# V1_EG7.net
KiCad netlist of a schematic drawn in EAGLE
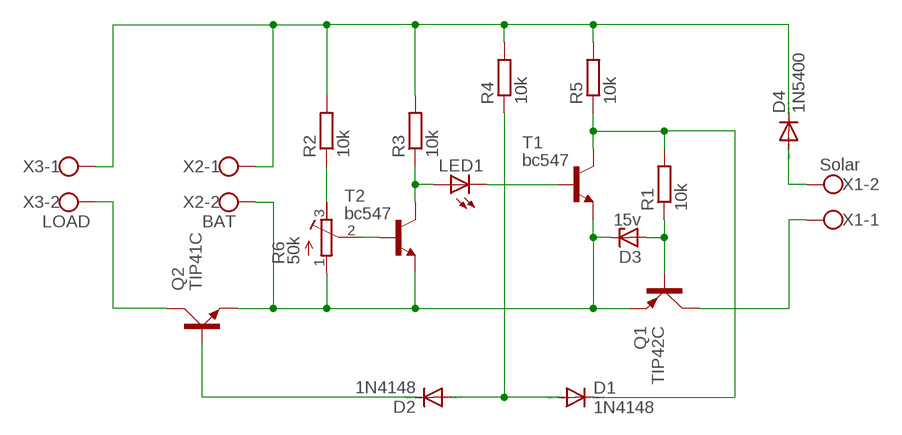
[diagram p0: schematic, sheet 1]

(export (version "E")
  (design (tool "Eeschema 10.0.6"))
  (components
    (comp (ref "D1")
      (value "1N4148")
      (footprint "eagle-import:DO35-10")
      (libsource (lib "eagle-import") (part "1N4148DO35-10"))
    )
    (comp (ref "D2")
      (value "1N4148")
      (footprint "eagle-import:DO35-10")
      (libsource (lib "eagle-import") (part "1N4148DO35-10"))
    )
    (comp (ref "D3")
      (value "15v")
      (footprint "eagle-import:ZDIO-10")
      (libsource (lib "eagle-import") (part "ZENER-DIODEZD-10"))
    )
    (comp (ref "D4")
      (value "1N5400")
      (footprint "eagle-import:DO201-15")
      (libsource (lib "eagle-import") (part "1N5400"))
    )
    (comp (ref "LED1")
      (value "LED5MM")
      (footprint "eagle-import:LED5MM")
      (libsource (lib "eagle-import") (part "LED5MM"))
    )
    (comp (ref "Q1")
      (value "TIP42C")
      (footprint "eagle-import:TO220AV")
      (libsource (lib "eagle-import") (part "TIP42C"))
    )
    (comp (ref "Q2")
      (value "TIP41C")
      (footprint "eagle-import:TO220AV")
      (libsource (lib "eagle-import") (part "TIP41C"))
    )
    (comp (ref "R1")
      (value "10k")
      (footprint "eagle-import:0207_10")
      (libsource (lib "eagle-import") (part "R-EU_0207/10"))
    )
    (comp (ref "R2")
      (value "10k")
      (footprint "eagle-import:0207_10")
      (libsource (lib "eagle-import") (part "R-EU_0207/10"))
    )
    (comp (ref "R3")
      (value "10k")
      (footprint "eagle-import:0207_10")
      (libsource (lib "eagle-import") (part "R-EU_0207/10"))
    )
    (comp (ref "R4")
      (value "10k")
      (footprint "eagle-import:0207_10")
      (libsource (lib "eagle-import") (part "R-EU_0207/10"))
    )
    (comp (ref "R5")
      (value "10k")
      (footprint "eagle-import:0207_10")
      (libsource (lib "eagle-import") (part "R-EU_0207/10"))
    )
    (comp (ref "R6")
      (value "50k")
      (footprint "eagle-import:RTRIM64W")
      (libsource (lib "eagle-import") (part "R-TRIMM64W"))
    )
    (comp (ref "T1")
      (value "bc547")
      (footprint "eagle-import:TO92-CBE")
      (libsource (lib "eagle-import") (part "-NPN-TO92-CBEBC547"))
    )
    (comp (ref "T2")
      (value "bc547")
      (footprint "eagle-import:TO92-CBE")
      (libsource (lib "eagle-import") (part "-NPN-TO92-CBEBC547"))
    )
    (comp (ref "X1")
      (value "Solar")
      (footprint "eagle-import:W237-102")
      (fields (field (name "MPN") "237-102"))
      (libsource (lib "eagle-import") (part "W237-102"))
    )
    (comp (ref "X2")
      (value "BAT")
      (footprint "eagle-import:W237-102")
      (fields (field (name "MPN") "237-102"))
      (libsource (lib "eagle-import") (part "W237-102"))
    )
    (comp (ref "X3")
      (value "LOAD")
      (footprint "eagle-import:W237-102")
      (fields (field (name "MPN") "237-102"))
      (libsource (lib "eagle-import") (part "W237-102"))
    )
  )
  (nets
    (net (code "1") (name "Net-(D1-PadA)") (class "Default")
      (node (ref "D1") (pin "A") (pinfunction "A_A") (pintype "passive"))
      (node (ref "D2") (pin "A") (pinfunction "A_A") (pintype "passive"))
      (node (ref "R4") (pin "1") (pinfunction "1_1") (pintype "passive"))
    )
    (net (code "2") (name "Net-(D1-PadC)") (class "Default")
      (node (ref "D1") (pin "C") (pinfunction "C_C") (pintype "passive"))
      (node (ref "R1") (pin "2") (pinfunction "2_2") (pintype "passive"))
      (node (ref "R5") (pin "1") (pinfunction "1_1") (pintype "passive"))
      (node (ref "T1") (pin "C") (pinfunction "C_C") (pintype "passive"))
    )
    (net (code "3") (name "Net-(D2-PadC)") (class "Default")
      (node (ref "D2") (pin "C") (pinfunction "C_C") (pintype "passive"))
      (node (ref "Q2") (pin "B") (pinfunction "B_B") (pintype "passive"))
    )
    (net (code "4") (name "Net-(D3-PadA)") (class "Default")
      (node (ref "D3") (pin "A") (pinfunction "A_A") (pintype "passive"))
      (node (ref "Q1") (pin "B") (pinfunction "B_B") (pintype "passive"))
      (node (ref "R1") (pin "1") (pinfunction "1_1") (pintype "passive"))
    )
    (net (code "5") (name "Net-(LED1-C)") (class "Default")
      (node (ref "LED1") (pin "K") (pinfunction "C_K") (pintype "passive"))
      (node (ref "T1") (pin "B") (pinfunction "B_B") (pintype "passive"))
    )
    (net (code "6") (name "Net-(LED1-PadA)") (class "Default")
      (node (ref "LED1") (pin "A") (pinfunction "A_A") (pintype "passive"))
      (node (ref "R3") (pin "1") (pinfunction "1_1") (pintype "passive"))
      (node (ref "T2") (pin "C") (pinfunction "C_C") (pintype "passive"))
    )
    (net (code "7") (name "Net-(R6-A)") (class "Default")
      (node (ref "D3") (pin "C") (pinfunction "C_C") (pintype "passive"))
      (node (ref "Q1") (pin "E") (pinfunction "E_E") (pintype "passive"))
      (node (ref "Q2") (pin "E") (pinfunction "E_E") (pintype "passive"))
      (node (ref "R6") (pin "1") (pinfunction "A_1") (pintype "passive"))
      (node (ref "T1") (pin "E") (pinfunction "E_E") (pintype "passive"))
      (node (ref "T2") (pin "E") (pinfunction "E_E") (pintype "passive"))
      (node (ref "X2") (pin "2") (pinfunction "KL_2") (pintype "passive"))
    )
    (net (code "8") (name "Net-(R6-E)") (class "Default")
      (node (ref "R2") (pin "1") (pinfunction "1_1") (pintype "passive"))
      (node (ref "R6") (pin "3") (pinfunction "E_3") (pintype "passive"))
    )
    (net (code "9") (name "Net-(R6-S)") (class "Default")
      (node (ref "R6") (pin "2") (pinfunction "S_2") (pintype "passive"))
      (node (ref "T2") (pin "B") (pinfunction "B_B") (pintype "passive"))
    )
    (net (code "10") (name "Net-(X1A-KL)") (class "Default")
      (node (ref "Q1") (pin "C") (pinfunction "C_C") (pintype "passive"))
      (node (ref "X1") (pin "1") (pinfunction "KL_1") (pintype "passive"))
    )
    (net (code "11") (name "Net-(X1B-KL)") (class "Default")
      (node (ref "D4") (pin "A") (pinfunction "A_A") (pintype "passive"))
      (node (ref "X1") (pin "2") (pinfunction "KL_2") (pintype "passive"))
    )
    (net (code "12") (name "Net-(X2A-KL)") (class "Default")
      (node (ref "D4") (pin "C") (pinfunction "C_C") (pintype "passive"))
      (node (ref "R2") (pin "2") (pinfunction "2_2") (pintype "passive"))
      (node (ref "R3") (pin "2") (pinfunction "2_2") (pintype "passive"))
      (node (ref "R4") (pin "2") (pinfunction "2_2") (pintype "passive"))
      (node (ref "R5") (pin "2") (pinfunction "2_2") (pintype "passive"))
      (node (ref "X2") (pin "1") (pinfunction "KL_1") (pintype "passive"))
      (node (ref "X3") (pin "1") (pinfunction "KL_1") (pintype "passive"))
    )
    (net (code "13") (name "Net-(X3B-KL)") (class "Default")
      (node (ref "Q2") (pin "C") (pinfunction "C_C") (pintype "passive"))
      (node (ref "X3") (pin "2") (pinfunction "KL_2") (pintype "passive"))
    )
  )
)
